# First_Project.net
KiCad netlist of a schematic drawn in EAGLE
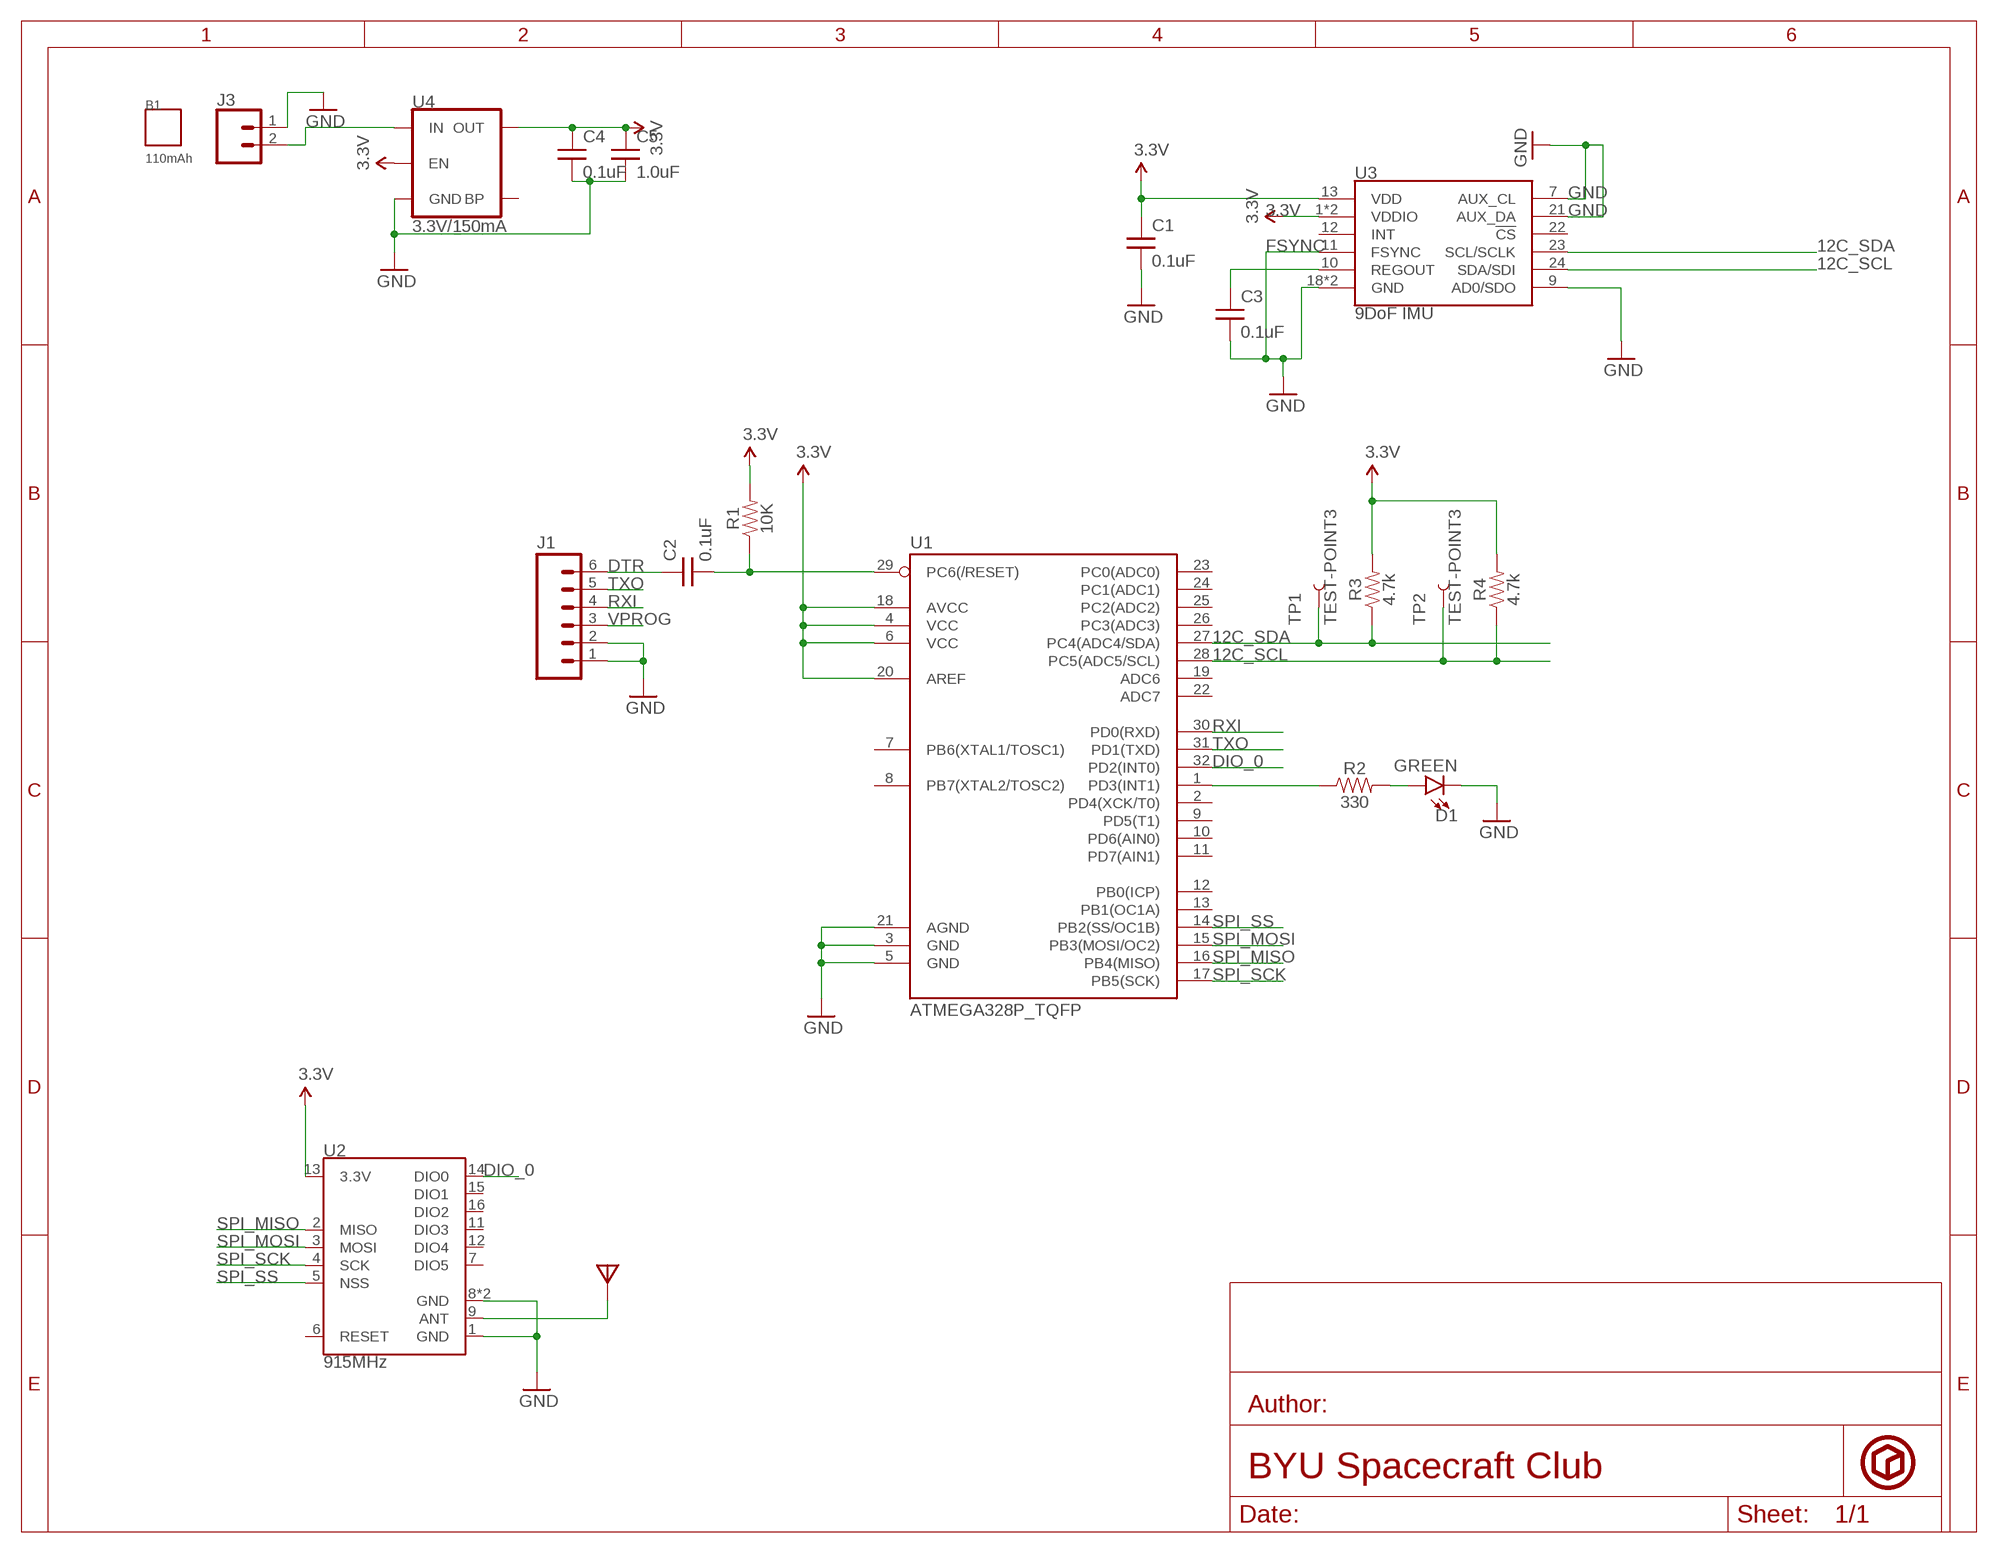
[diagram p0: schematic, sheet 1]

(export (version "E")
  (design (tool "Eeschema 10.0.6"))
  (components
    (comp (ref "ANT1")
      (value "ANTENNA_PAD")
      (footprint "eagle-import:RFM12B-ANTENNA")
      (libsource (lib "eagle-import") (part "ANTENNA_PAD"))
    )
    (comp (ref "B1")
      (value "110mAh")
      (footprint "eagle-import:BATT_110MAH")
      (libsource (lib "eagle-import") (part "BATTERY_FOOTPRINT"))
    )
    (comp (ref "C1")
      (value "0.1uF")
      (footprint "eagle-import:0603-CAP")
      (libsource (lib "eagle-import") (part "CAPACITOR_0.1UF"))
    )
    (comp (ref "C2")
      (value "0.1uF")
      (footprint "eagle-import:0603-CAP")
      (libsource (lib "eagle-import") (part "CAPACITOR_0.1UF"))
    )
    (comp (ref "C3")
      (value "0.1uF")
      (footprint "eagle-import:0603-CAP")
      (libsource (lib "eagle-import") (part "CAPACITOR_0.1UF"))
    )
    (comp (ref "C4")
      (value "0.1uF")
      (footprint "eagle-import:0603-CAP")
      (libsource (lib "eagle-import") (part "CAPACITOR_0.1UF"))
    )
    (comp (ref "C5")
      (value "1.0uF")
      (footprint "eagle-import:0603")
      (libsource (lib "eagle-import") (part "CAPACITOR_1.0UF-0603-16V-10%"))
    )
    (comp (ref "D1")
      (value "GREEN")
      (footprint "eagle-import:LED-0603")
      (libsource (lib "eagle-import") (part "LED_GREEN0603"))
    )
    (comp (ref "J1")
      (value "CONNECTOR_6PINSILK_FEMALE_PTH")
      (footprint "eagle-import:1X06")
      (libsource (lib "eagle-import") (part "CONNECTOR_6PINSILK_FEMALE_PTH"))
    )
    (comp (ref "J3")
      (value "CONNECTOR_2PIN-JST-2MM-SMT")
      (footprint "eagle-import:JST-2-SMD")
      (libsource (lib "eagle-import") (part "CONNECTOR_2PIN-JST-2MM-SMT"))
    )
    (comp (ref "R1")
      (value "10K")
      (footprint "eagle-import:0603-RES")
      (libsource (lib "eagle-import") (part "RESISTOR_10KOHM0603"))
    )
    (comp (ref "R2")
      (value "330")
      (footprint "eagle-import:0603")
      (libsource (lib "eagle-import") (part "RESISTOR_330OHM-0603-1/10W-1%"))
    )
    (comp (ref "R3")
      (value "4.7k")
      (footprint "eagle-import:0603")
      (libsource (lib "eagle-import") (part "RESISTOR_4.7KOHM-0603-1/10W-1%"))
    )
    (comp (ref "R4")
      (value "4.7k")
      (footprint "eagle-import:0603")
      (libsource (lib "eagle-import") (part "RESISTOR_4.7KOHM-0603-1/10W-1%"))
    )
    (comp (ref "TP1")
      (value "TEST-POINT3")
      (footprint "eagle-import:PAD.03X.03")
      (libsource (lib "eagle-import") (part "TEST-POINT3"))
    )
    (comp (ref "TP2")
      (value "TEST-POINT3")
      (footprint "eagle-import:PAD.03X.03")
      (libsource (lib "eagle-import") (part "TEST-POINT3"))
    )
    (comp (ref "U1")
      (value "ATMEGA328P_TQFP")
      (footprint "eagle-import:TQFP32-08")
      (libsource (lib "eagle-import") (part "ATMEGA328P_TQFP"))
    )
    (comp (ref "U2")
      (value "915MHz")
      (footprint "eagle-import:RFM69HCW-XXXS2")
      (libsource (lib "eagle-import") (part "RADIO_RFM69HCW-915"))
    )
    (comp (ref "U3")
      (value "9DoF IMU")
      (footprint "eagle-import:QFN24-3X3")
      (libsource (lib "eagle-import") (part "MPU9250"))
    )
    (comp (ref "U4")
      (value "3.3V/150mA")
      (footprint "eagle-import:SOT23-5")
      (libsource (lib "eagle-import") (part "VOLTAGE_REGULATOR_MIC52053.3V"))
    )
  )
  (nets
    (net (code "1") (name "/12C_SCL") (class "Default")
      (node (ref "R4") (pin "1") (pinfunction "1_1") (pintype "passive"))
      (node (ref "TP2") (pin "P$1") (pinfunction "1_P$1") (pintype "bidirectional"))
      (node (ref "U1") (pin "28") (pinfunction "PC5(ADC5/SCL)_28") (pintype "bidirectional"))
      (node (ref "U3") (pin "24") (pinfunction "SDA/SDI_24") (pintype "bidirectional"))
    )
    (net (code "2") (name "/12C_SDA") (class "Default")
      (node (ref "R3") (pin "1") (pinfunction "1_1") (pintype "passive"))
      (node (ref "TP1") (pin "P$1") (pinfunction "1_P$1") (pintype "bidirectional"))
      (node (ref "U1") (pin "27") (pinfunction "PC4(ADC4/SDA)_27") (pintype "bidirectional"))
      (node (ref "U3") (pin "23") (pinfunction "SCL/SCLK_23") (pintype "bidirectional"))
    )
    (net (code "3") (name "/DIO_0") (class "Default")
      (node (ref "U1") (pin "32") (pinfunction "PD2(INT0)_32") (pintype "bidirectional"))
      (node (ref "U2") (pin "14") (pinfunction "DIO0_14") (pintype "bidirectional"))
    )
    (net (code "4") (name "/DTR") (class "Default")
      (node (ref "C2") (pin "1") (pinfunction "1_1") (pintype "passive"))
      (node (ref "J1") (pin "6") (pinfunction "6_6") (pintype "passive"))
    )
    (net (code "5") (name "/FSYNC") (class "Default")
      (node (ref "C3") (pin "1") (pinfunction "1_1") (pintype "passive"))
      (node (ref "U3") (pin "10") (pinfunction "REGOUT_10") (pintype "bidirectional"))
    )
    (net (code "6") (name "/RXI") (class "Default")
      (node (ref "J1") (pin "4") (pinfunction "4_4") (pintype "passive"))
      (node (ref "U1") (pin "30") (pinfunction "PD0(RXD)_30") (pintype "bidirectional"))
    )
    (net (code "7") (name "/SPI_MISO") (class "Default")
      (node (ref "U1") (pin "16") (pinfunction "PB4(MISO)_16") (pintype "bidirectional"))
      (node (ref "U2") (pin "2") (pinfunction "MISO_2") (pintype "bidirectional"))
    )
    (net (code "8") (name "/SPI_MOSI") (class "Default")
      (node (ref "U1") (pin "15") (pinfunction "PB3(MOSI/OC2)_15") (pintype "bidirectional"))
      (node (ref "U2") (pin "3") (pinfunction "MOSI_3") (pintype "input"))
    )
    (net (code "9") (name "/SPI_SCK") (class "Default")
      (node (ref "U1") (pin "17") (pinfunction "PB5(SCK)_17") (pintype "bidirectional"))
      (node (ref "U2") (pin "4") (pinfunction "SCK_4") (pintype "input"))
    )
    (net (code "10") (name "/SPI_SS") (class "Default")
      (node (ref "U1") (pin "14") (pinfunction "PB2(SS/OC1B)_14") (pintype "bidirectional"))
      (node (ref "U2") (pin "5") (pinfunction "NSS_5") (pintype "input"))
    )
    (net (code "11") (name "/TXO") (class "Default")
      (node (ref "J1") (pin "5") (pinfunction "5_5") (pintype "passive"))
      (node (ref "U1") (pin "31") (pinfunction "PD1(TXD)_31") (pintype "bidirectional"))
    )
    (net (code "12") (name "/VPROG") (class "Default")
      (node (ref "J1") (pin "3") (pinfunction "3_3") (pintype "passive"))
    )
    (net (code "13") (name "3.3V") (class "Default")
      (node (ref "C1") (pin "1") (pinfunction "1_1") (pintype "passive"))
      (node (ref "C4") (pin "1") (pinfunction "1_1") (pintype "passive"))
      (node (ref "C5") (pin "1") (pinfunction "1_1") (pintype "passive"))
      (node (ref "R1") (pin "2") (pinfunction "2_2") (pintype "passive"))
      (node (ref "R3") (pin "2") (pinfunction "2_2") (pintype "passive"))
      (node (ref "R4") (pin "2") (pinfunction "2_2") (pintype "passive"))
      (node (ref "U1") (pin "18") (pinfunction "AVCC_18") (pintype "bidirectional"))
      (node (ref "U1") (pin "20") (pinfunction "AREF_20") (pintype "bidirectional"))
      (node (ref "U1") (pin "4") (pinfunction "VCC_4") (pintype "bidirectional"))
      (node (ref "U1") (pin "6") (pinfunction "VCC_6") (pintype "bidirectional"))
      (node (ref "U2") (pin "13") (pinfunction "3.3V_13") (pintype "power_in"))
      (node (ref "U3") (pin "1") (pinfunction "VDDIO_1") (pintype "bidirectional"))
      (node (ref "U3") (pin "13") (pinfunction "VDD_13") (pintype "bidirectional"))
      (node (ref "U3") (pin "8") (pinfunction "VDDIO_8") (pintype "bidirectional"))
      (node (ref "U4") (pin "3") (pinfunction "EN_3") (pintype "input"))
      (node (ref "U4") (pin "5") (pinfunction "OUT_5") (pintype "passive"))
    )
    (net (code "14") (name "GND") (class "Default")
      (node (ref "C1") (pin "2") (pinfunction "2_2") (pintype "passive"))
      (node (ref "C3") (pin "2") (pinfunction "2_2") (pintype "passive"))
      (node (ref "C4") (pin "2") (pinfunction "2_2") (pintype "passive"))
      (node (ref "C5") (pin "2") (pinfunction "2_2") (pintype "passive"))
      (node (ref "D1") (pin "C") (pinfunction "C_C") (pintype "passive"))
      (node (ref "J1") (pin "1") (pinfunction "1_1") (pintype "passive"))
      (node (ref "J1") (pin "2") (pinfunction "2_2") (pintype "passive"))
      (node (ref "J3") (pin "1") (pinfunction "2_1") (pintype "passive"))
      (node (ref "U1") (pin "21") (pinfunction "AGND_21") (pintype "bidirectional"))
      (node (ref "U1") (pin "3") (pinfunction "GND_3") (pintype "bidirectional"))
      (node (ref "U1") (pin "5") (pinfunction "GND_5") (pintype "bidirectional"))
      (node (ref "U2") (pin "1") (pinfunction "GND_1") (pintype "power_in"))
      (node (ref "U2") (pin "10") (pinfunction "GND_10") (pintype "power_in"))
      (node (ref "U2") (pin "8") (pinfunction "GND_8") (pintype "power_in"))
      (node (ref "U3") (pin "11") (pinfunction "FSYNC_11") (pintype "bidirectional"))
      (node (ref "U3") (pin "18") (pinfunction "GND_18") (pintype "bidirectional"))
      (node (ref "U3") (pin "20") (pinfunction "GND_20") (pintype "bidirectional"))
      (node (ref "U3") (pin "21") (pinfunction "AUX_DA_21") (pintype "bidirectional"))
      (node (ref "U3") (pin "7") (pinfunction "AUX_CL_7") (pintype "bidirectional"))
      (node (ref "U3") (pin "9") (pinfunction "AD0/SDO_9") (pintype "bidirectional"))
      (node (ref "U4") (pin "2") (pinfunction "GND_2") (pintype "input"))
    )
    (net (code "15") (name "Net-(ANT1-1)") (class "Default")
      (node (ref "ANT1") (pin "P$1") (pinfunction "1_P$1") (pintype "bidirectional"))
      (node (ref "U2") (pin "9") (pinfunction "ANT_9") (pintype "passive"))
    )
    (net (code "16") (name "Net-(D1-PadA)") (class "Default")
      (node (ref "D1") (pin "A") (pinfunction "A_A") (pintype "passive"))
      (node (ref "R2") (pin "2") (pinfunction "2_2") (pintype "passive"))
    )
    (net (code "17") (name "Net-(J3-1)") (class "Default")
      (node (ref "J3") (pin "2") (pinfunction "1_2") (pintype "passive"))
      (node (ref "U4") (pin "1") (pinfunction "IN_1") (pintype "input"))
    )
    (net (code "18") (name "Net-(U1-PC6({slash}RESET))") (class "Default")
      (node (ref "C2") (pin "2") (pinfunction "2_2") (pintype "passive"))
      (node (ref "R1") (pin "1") (pinfunction "1_1") (pintype "passive"))
      (node (ref "U1") (pin "29") (pinfunction "PC6(/RESET)_29") (pintype "bidirectional"))
    )
    (net (code "19") (name "Net-(U1-PD3(INT1))") (class "Default")
      (node (ref "R2") (pin "1") (pinfunction "1_1") (pintype "passive"))
      (node (ref "U1") (pin "1") (pinfunction "PD3(INT1)_1") (pintype "bidirectional"))
    )
    (net (code "20") (name "unconnected-(U1-ADC6-Pad19)") (class "Default")
      (node (ref "U1") (pin "19") (pinfunction "ADC6_19") (pintype "bidirectional"))
    )
    (net (code "21") (name "unconnected-(U1-ADC7-Pad22)") (class "Default")
      (node (ref "U1") (pin "22") (pinfunction "ADC7_22") (pintype "bidirectional"))
    )
    (net (code "22") (name "unconnected-(U1-PB0(ICP)-Pad12)") (class "Default")
      (node (ref "U1") (pin "12") (pinfunction "PB0(ICP)_12") (pintype "bidirectional"))
    )
    (net (code "23") (name "unconnected-(U1-PB1(OC1A)-Pad13)") (class "Default")
      (node (ref "U1") (pin "13") (pinfunction "PB1(OC1A)_13") (pintype "bidirectional"))
    )
    (net (code "24") (name "unconnected-(U1-PB6(XTAL1{slash}TOSC1)-Pad7)") (class "Default")
      (node (ref "U1") (pin "7") (pinfunction "PB6(XTAL1/TOSC1)_7") (pintype "bidirectional"))
    )
    (net (code "25") (name "unconnected-(U1-PB7(XTAL2{slash}TOSC2)-Pad8)") (class "Default")
      (node (ref "U1") (pin "8") (pinfunction "PB7(XTAL2/TOSC2)_8") (pintype "bidirectional"))
    )
    (net (code "26") (name "unconnected-(U1-PC0(ADC0)-Pad23)") (class "Default")
      (node (ref "U1") (pin "23") (pinfunction "PC0(ADC0)_23") (pintype "bidirectional"))
    )
    (net (code "27") (name "unconnected-(U1-PC1(ADC1)-Pad24)") (class "Default")
      (node (ref "U1") (pin "24") (pinfunction "PC1(ADC1)_24") (pintype "bidirectional"))
    )
    (net (code "28") (name "unconnected-(U1-PC2(ADC2)-Pad25)") (class "Default")
      (node (ref "U1") (pin "25") (pinfunction "PC2(ADC2)_25") (pintype "bidirectional"))
    )
    (net (code "29") (name "unconnected-(U1-PC3(ADC3)-Pad26)") (class "Default")
      (node (ref "U1") (pin "26") (pinfunction "PC3(ADC3)_26") (pintype "bidirectional"))
    )
    (net (code "30") (name "unconnected-(U1-PD4(XCK{slash}T0)-Pad2)") (class "Default")
      (node (ref "U1") (pin "2") (pinfunction "PD4(XCK/T0)_2") (pintype "bidirectional"))
    )
    (net (code "31") (name "unconnected-(U1-PD5(T1)-Pad9)") (class "Default")
      (node (ref "U1") (pin "9") (pinfunction "PD5(T1)_9") (pintype "bidirectional"))
    )
    (net (code "32") (name "unconnected-(U1-PD6(AIN0)-Pad10)") (class "Default")
      (node (ref "U1") (pin "10") (pinfunction "PD6(AIN0)_10") (pintype "bidirectional"))
    )
    (net (code "33") (name "unconnected-(U1-PD7(AIN1)-Pad11)") (class "Default")
      (node (ref "U1") (pin "11") (pinfunction "PD7(AIN1)_11") (pintype "bidirectional"))
    )
    (net (code "34") (name "unconnected-(U2-DIO1-Pad15)") (class "Default")
      (node (ref "U2") (pin "15") (pinfunction "DIO1_15") (pintype "bidirectional"))
    )
    (net (code "35") (name "unconnected-(U2-DIO2-Pad16)") (class "Default")
      (node (ref "U2") (pin "16") (pinfunction "DIO2_16") (pintype "bidirectional"))
    )
    (net (code "36") (name "unconnected-(U2-DIO3-Pad11)") (class "Default")
      (node (ref "U2") (pin "11") (pinfunction "DIO3_11") (pintype "bidirectional"))
    )
    (net (code "37") (name "unconnected-(U2-DIO4-Pad12)") (class "Default")
      (node (ref "U2") (pin "12") (pinfunction "DIO4_12") (pintype "bidirectional"))
    )
    (net (code "38") (name "unconnected-(U2-DIO5-Pad7)") (class "Default")
      (node (ref "U2") (pin "7") (pinfunction "DIO5_7") (pintype "bidirectional"))
    )
    (net (code "39") (name "unconnected-(U2-RESET-Pad6)") (class "Default")
      (node (ref "U2") (pin "6") (pinfunction "RESET_6") (pintype "input"))
    )
    (net (code "40") (name "unconnected-(U3-INT-Pad12)") (class "Default")
      (node (ref "U3") (pin "12") (pinfunction "INT_12") (pintype "bidirectional"))
    )
    (net (code "41") (name "unconnected-(U3-~{CS}-Pad22)") (class "Default")
      (node (ref "U3") (pin "22") (pinfunction "~{CS}_22") (pintype "bidirectional"))
    )
    (net (code "42") (name "unconnected-(U4-BP-Pad4)") (class "Default")
      (node (ref "U4") (pin "4") (pinfunction "BP_4") (pintype "input"))
    )
  )
)
